# Opto_inputs.net
KiCad netlist of a schematic drawn in Altium Designer
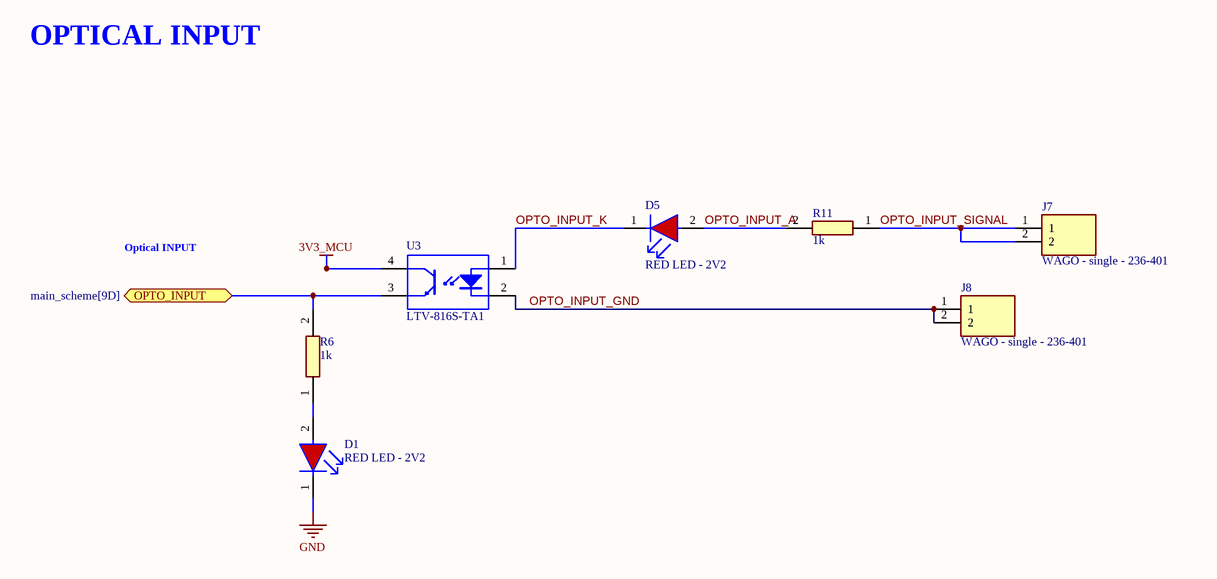
[diagram p0: Opto_inputs.SchDoc]

(export (version "E")
  (design (tool "Eeschema 10.0.6"))
  (components
    (comp (ref "D1")
      (value "RED LED - 2V2")
      (footprint "0603_RED_LED")
      (description "LED RED DIFFUSED 0603 SMD")
      (fields (field (name "PARTNUMBER") "SML-D12U1WT86"))
      (libsource (lib "Schlib1") (part "LED - 0603 - RED - 2V2"))
    )
    (comp (ref "D5")
      (value "RED LED - 2V2")
      (footprint "0603_RED_LED")
      (description "LED RED DIFFUSED 0603 SMD")
      (fields (field (name "PARTNUMBER") "SML-D12U1WT86"))
      (libsource (lib "Schlib1") (part "LED - 0603 - RED - 2V2"))
    )
    (comp (ref "J7")
      (value "WAGO - single - 236-401")
      (footprint "PcbLib1:WAGO-236-601")
      (description "Wago connector - PCB to wire - single - 24A 320V")
      (fields (field (name "PARTNUMBER") "236-401"))
      (libsource (lib "Schlib1") (part "WAGO - single - 236-401"))
    )
    (comp (ref "J8")
      (value "WAGO - single - 236-401")
      (footprint "PcbLib1:WAGO-236-601")
      (description "Wago connector - PCB to wire - single - 24A 320V")
      (fields (field (name "PARTNUMBER") "236-401"))
      (libsource (lib "Schlib1") (part "WAGO - single - 236-401"))
    )
    (comp (ref "R6")
      (value "1k")
      (footprint "PcbLib1:0603- SMD resistor")
      (description "Resistor 0603 1KR 100mW 1%")
      (fields (field (name "PARTNUMBER") "RT0603FRE071KL"))
      (libsource (lib "") (part "RESISTOR - 0603 - 1k_1"))
    )
    (comp (ref "R11")
      (value "1k")
      (footprint "PcbLib1:0603- SMD resistor")
      (description "Resistor 0603 1KR 100mW 1%")
      (fields (field (name "PARTNUMBER") "RT0603FRE071KL"))
      (libsource (lib "Schlib1") (part "RESISTOR - 0603 - 1k"))
    )
    (comp (ref "U3")
      (value "LTV-816S-TA1")
      (footprint "LTST-LTV-816S_V")
      (description "Photocoupler, 50 mA, -30 to 110 degC, 4-Pin SMD, RoHS, Tape and Reel")
      (libsource (lib "Schlib1") (part "OPTO - 50mA - 80V"))
    )
  )
  (nets
    (net (code "1") (name "/OPTO_INPUT") (class "Default")
      (node (ref "R6") (pin "2") (pinfunction "2_2") (pintype "passive"))
      (node (ref "U3") (pin "3") (pinfunction "EMITTER_3") (pintype "passive"))
    )
    (net (code "2") (name "/OPTO_INPUT_A") (class "Default")
      (node (ref "D5") (pin "2") (pinfunction "A_2") (pintype "passive"))
      (node (ref "R11") (pin "2") (pinfunction "2_2") (pintype "passive"))
    )
    (net (code "3") (name "/OPTO_INPUT_GND") (class "Default")
      (node (ref "J8") (pin "1") (pinfunction "1_1") (pintype "passive"))
      (node (ref "J8") (pin "2") (pinfunction "2_2") (pintype "passive"))
      (node (ref "U3") (pin "2") (pinfunction "CATHODE_2") (pintype "passive"))
    )
    (net (code "4") (name "/OPTO_INPUT_K") (class "Default")
      (node (ref "D5") (pin "1") (pinfunction "C_1") (pintype "passive"))
      (node (ref "U3") (pin "1") (pinfunction "ANODE_1") (pintype "passive"))
    )
    (net (code "5") (name "/OPTO_INPUT_SIGNAL") (class "Default")
      (node (ref "J7") (pin "1") (pinfunction "1_1") (pintype "passive"))
      (node (ref "J7") (pin "2") (pinfunction "2_2") (pintype "passive"))
      (node (ref "R11") (pin "1") (pinfunction "1_1") (pintype "passive"))
    )
    (net (code "6") (name "3V3_MCU") (class "Default")
      (node (ref "U3") (pin "4") (pinfunction "COLLECTOR_4") (pintype "passive"))
    )
    (net (code "7") (name "GND") (class "Default")
      (node (ref "D1") (pin "1") (pinfunction "C_1") (pintype "passive"))
    )
    (net (code "8") (name "Net-(D1-A)") (class "Default")
      (node (ref "D1") (pin "2") (pinfunction "A_2") (pintype "passive"))
      (node (ref "R6") (pin "1") (pinfunction "1_1") (pintype "passive"))
    )
  )
)
